# SiPM_ASSY_6x6mm.net
KiCad netlist of a schematic drawn in Altium Designer
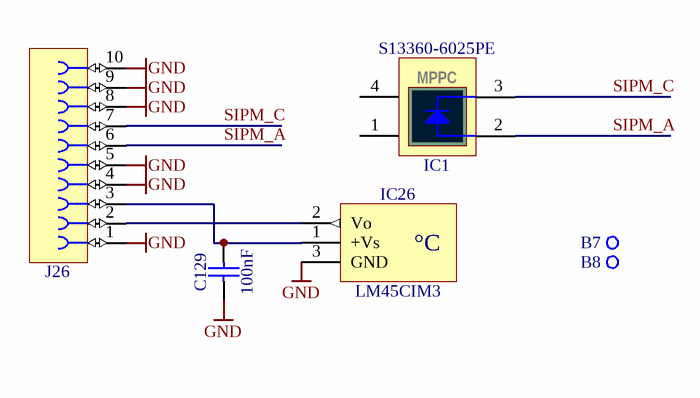
[diagram p0: SiPM_ASSY_6x6mm.SchDoc]

(export (version "E")
  (design (tool "Eeschema 10.0.6"))
  (components
    (comp (ref "B7")
      (value "Plated Hole")
      (footprint "MTG270_500")
      (description "Single Terminal Socket")
      (fields (field (name "PART NUMBER") "PLATED_HOLE2.7_PAD5.0") (field (name "AUTHOR") "CERN DEM JMW"))
      (libsource (lib "Eletro-mechanical") (part "Single Terminal Socket"))
    )
    (comp (ref "B8")
      (value "Plated Hole")
      (footprint "MTG270_500")
      (description "Single Terminal Socket")
      (fields (field (name "PART NUMBER") "PLATED_HOLE2.7_PAD5.0") (field (name "AUTHOR") "CERN DEM JMW"))
      (libsource (lib "Eletro-mechanical") (part "Single Terminal Socket"))
    )
    (comp (ref "C129")
      (value "100nF")
      (footprint "CAPC1005X55N")
      (description "Non-polarised capacitor")
      (fields
        (field (name "PART NUMBER") "CC0402_100NF_16V_10%_X7R")
        (field (name "VOLTAGE") "16V")
        (field (name "AUTHOR") "CERN DEM JLC")
      )
      (libsource (lib "Capacitors") (part "Capacitor - non polarized"))
    )
    (comp (ref "IC1")
      (value "S13360-6025PE")
      (footprint "HAMAMATSU_S13360-6025PE")
      (description "MPPC (Multi-Pixel Photon Counter)")
      (fields (field (name "MANUFACTURER") "HAMAMATSU") (field (name "AUTHOR") "CERN DEM BC"))
      (libsource (lib "Sensors") (part "SENS_MPPC_S13360-6025PE"))
    )
    (comp (ref "IC26")
      (value "LM45CIM3")
      (footprint "SOT95P251X112-3N")
      (description "-20° to +100°C ±3°C Precision Centigrade Temperature Sensors")
      (fields (field (name "MANUFACTURER") "NATIONAL SEMICONDUCTOR") (field (name "AUTHOR") "CERN DEM JLC"))
      (libsource (lib "ICs And Semiconductors") (part "LM45"))
    )
    (comp (ref "J26")
      (value "FFC/FPC")
      (footprint "MOLEX_52745-1097")
      (description "Connector 10 Female")
      (fields
        (field (name "PART NUMBER") "MOLEX_52745-1097")
        (field (name "MANUFACTURER") "MOLEX")
        (field (name "AUTHOR") "CERN DEM JLC")
      )
      (libsource (lib "Connectors") (part "Connector 10 Female"))
    )
  )
  (nets
    (net (code "1") (name "/SIPM_A") (class "Default")
      (node (ref "IC1") (pin "2") (pinfunction "A_2") (pintype "passive"))
      (node (ref "J26") (pin "6") (pinfunction "6_6") (pintype "bidirectional"))
    )
    (net (code "2") (name "/SIPM_C") (class "Default")
      (node (ref "IC1") (pin "3") (pinfunction "C_3") (pintype "passive"))
      (node (ref "J26") (pin "7") (pinfunction "7_7") (pintype "bidirectional"))
    )
    (net (code "3") (name "GND") (class "Default")
      (node (ref "C129") (pin "1") (pinfunction "1_1") (pintype "passive"))
      (node (ref "IC26") (pin "3") (pinfunction "GND_3") (pintype "power_in"))
      (node (ref "J26") (pin "1") (pinfunction "1_1") (pintype "bidirectional"))
      (node (ref "J26") (pin "10") (pinfunction "10_10") (pintype "bidirectional"))
      (node (ref "J26") (pin "4") (pinfunction "4_4") (pintype "bidirectional"))
      (node (ref "J26") (pin "5") (pinfunction "5_5") (pintype "bidirectional"))
      (node (ref "J26") (pin "8") (pinfunction "8_8") (pintype "bidirectional"))
      (node (ref "J26") (pin "9") (pinfunction "9_9") (pintype "bidirectional"))
    )
    (net (code "4") (name "Net-(IC26-+Vs)") (class "Default")
      (node (ref "C129") (pin "2") (pinfunction "2_2") (pintype "passive"))
      (node (ref "IC26") (pin "1") (pinfunction "+Vs_1") (pintype "power_in"))
      (node (ref "J26") (pin "3") (pinfunction "3_3") (pintype "bidirectional"))
    )
    (net (code "5") (name "Net-(IC26-Vo)") (class "Default")
      (node (ref "IC26") (pin "2") (pinfunction "Vo_2") (pintype "output"))
      (node (ref "J26") (pin "2") (pinfunction "2_2") (pintype "bidirectional"))
    )
    (net (code "6") (name "unconnected-(B7-Pad1)") (class "Default")
      (node (ref "B7") (pin "1") (pinfunction "1_1") (pintype "bidirectional"))
    )
    (net (code "7") (name "unconnected-(B8-Pad1)") (class "Default")
      (node (ref "B8") (pin "1") (pinfunction "1_1") (pintype "bidirectional"))
    )
    (net (code "8") (name "unconnected-(IC1-NC-Pad1)") (class "Default")
      (node (ref "IC1") (pin "1") (pinfunction "NC_1") (pintype "passive"))
    )
    (net (code "9") (name "unconnected-(IC1-NC-Pad4)") (class "Default")
      (node (ref "IC1") (pin "4") (pinfunction "NC_4") (pintype "passive"))
    )
  )
)
